# clickclack-mk-1_1-a.net
KiCad netlist of a schematic drawn in EAGLE
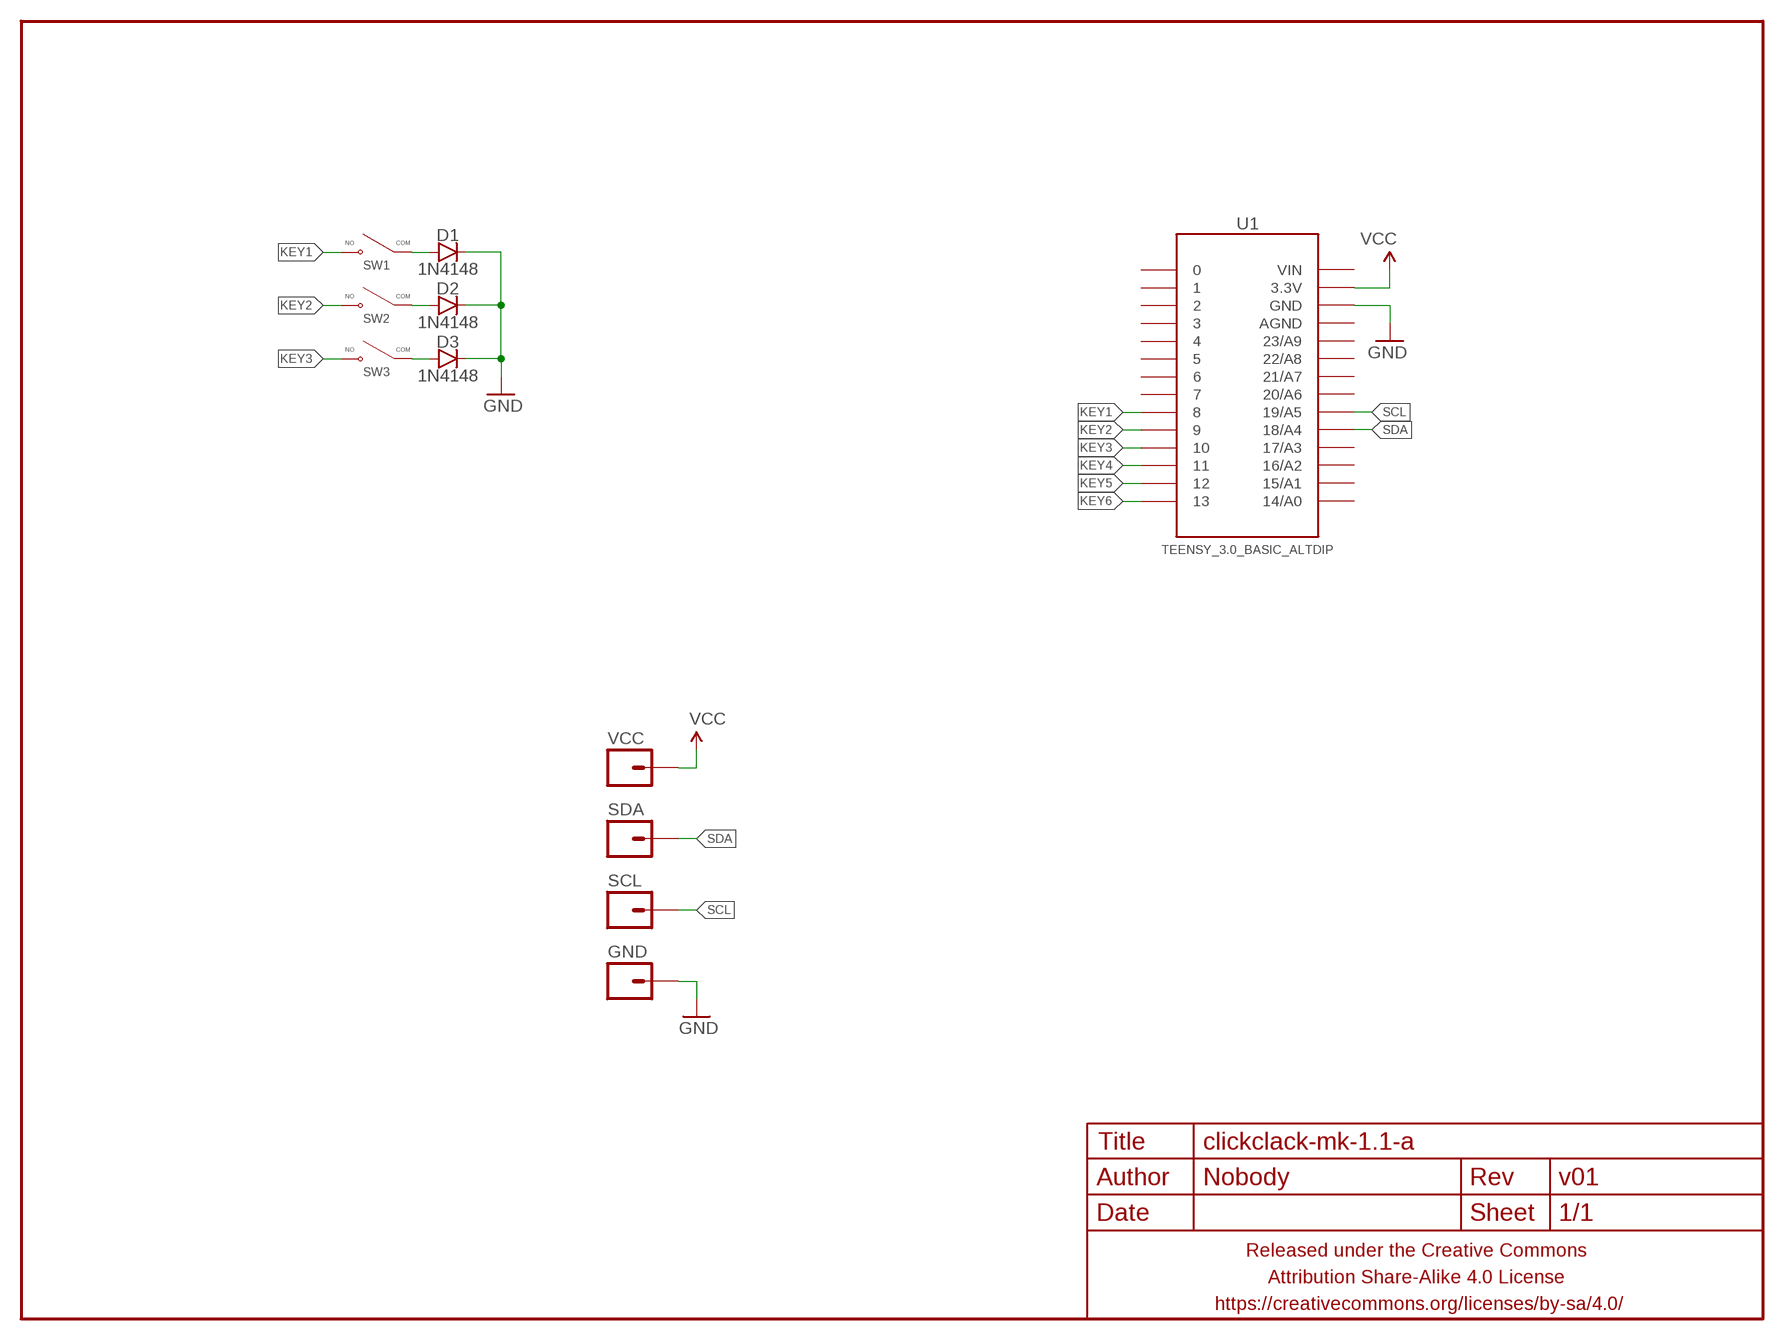
[diagram p0: schematic, sheet 1]

(export (version "E")
  (design (tool "Eeschema 10.0.6"))
  (components
    (comp (ref "D1")
      (value "1N4148")
      (footprint "eagle-import:DIODE-7.62MM")
      (libsource (lib "eagle-import") (part "DIODEPTH-7.62MM"))
    )
    (comp (ref "D2")
      (value "1N4148")
      (footprint "eagle-import:DIODE-7.62MM")
      (libsource (lib "eagle-import") (part "DIODEPTH-7.62MM"))
    )
    (comp (ref "D3")
      (value "1N4148")
      (footprint "eagle-import:DIODE-7.62MM")
      (libsource (lib "eagle-import") (part "DIODEPTH-7.62MM"))
    )
    (comp (ref "FRAME1")
      (value "FRAME-LETTERNO_PACKAGE")
      (footprint "eagle-import:DUMMY")
      (fields (field (name "DESIGNER") "Nobody"))
      (libsource (lib "eagle-import") (part "FRAME-LETTERNO_PACKAGE"))
    )
    (comp (ref "GND")
      (value "M01PTH")
      (footprint "eagle-import:1X01")
      (libsource (lib "eagle-import") (part "M01PTH"))
    )
    (comp (ref "SCL")
      (value "M01PTH")
      (footprint "eagle-import:1X01")
      (libsource (lib "eagle-import") (part "M01PTH"))
    )
    (comp (ref "SDA")
      (value "M01PTH")
      (footprint "eagle-import:1X01")
      (libsource (lib "eagle-import") (part "M01PTH"))
    )
    (comp (ref "SW1")
      (value "CHERRY-MXNONUBS")
      (footprint "eagle-import:CHERRY-MX-NONUBS")
      (libsource (lib "eagle-import") (part "CHERRY-MXNONUBS"))
    )
    (comp (ref "SW2")
      (value "CHERRY-MXNONUBS")
      (footprint "eagle-import:CHERRY-MX-NONUBS")
      (libsource (lib "eagle-import") (part "CHERRY-MXNONUBS"))
    )
    (comp (ref "SW3")
      (value "CHERRY-MXNONUBS")
      (footprint "eagle-import:CHERRY-MX-NONUBS")
      (libsource (lib "eagle-import") (part "CHERRY-MXNONUBS"))
    )
    (comp (ref "U1")
      (value "TEENSY_3.0_BASIC_ALTDIP")
      (footprint "eagle-import:TEENSY_3.0_BASIC_ALT2")
      (libsource (lib "eagle-import") (part "TEENSY_3.0_BASIC_ALTDIP"))
    )
    (comp (ref "VCC")
      (value "M01PTH")
      (footprint "eagle-import:1X01")
      (libsource (lib "eagle-import") (part "M01PTH"))
    )
  )
  (nets
    (net (code "1") (name "/AGND") (class "Default")
      (node (ref "U1") (pin "AGND") (pinfunction "AGND_AGND") (pintype "power_in"))
    )
    (net (code "2") (name "/VIN") (class "Default")
      (node (ref "U1") (pin "VIN") (pinfunction "VIN_VIN") (pintype "power_in"))
    )
    (net (code "3") (name "GND") (class "Default")
      (node (ref "D1") (pin "K") (pinfunction "C_K") (pintype "passive"))
      (node (ref "D2") (pin "K") (pinfunction "C_K") (pintype "passive"))
      (node (ref "D3") (pin "K") (pinfunction "C_K") (pintype "passive"))
      (node (ref "GND") (pin "1") (pinfunction "1_1") (pintype "passive"))
      (node (ref "U1") (pin "GND") (pinfunction "GND_GND") (pintype "power_in"))
    )
    (net (code "4") (name "KEY1") (class "Default")
      (node (ref "SW1") (pin "2") (pinfunction "NO_2") (pintype "bidirectional"))
      (node (ref "U1") (pin "8") (pinfunction "8_8") (pintype "bidirectional"))
    )
    (net (code "5") (name "KEY2") (class "Default")
      (node (ref "SW2") (pin "2") (pinfunction "NO_2") (pintype "bidirectional"))
      (node (ref "U1") (pin "9") (pinfunction "9_9") (pintype "bidirectional"))
    )
    (net (code "6") (name "KEY3") (class "Default")
      (node (ref "SW3") (pin "2") (pinfunction "NO_2") (pintype "bidirectional"))
      (node (ref "U1") (pin "10") (pinfunction "10_10") (pintype "bidirectional"))
    )
    (net (code "7") (name "KEY4") (class "Default")
      (node (ref "U1") (pin "11") (pinfunction "11_11") (pintype "bidirectional"))
    )
    (net (code "8") (name "KEY5") (class "Default")
      (node (ref "U1") (pin "12") (pinfunction "12_12") (pintype "bidirectional"))
    )
    (net (code "9") (name "KEY6") (class "Default")
      (node (ref "U1") (pin "13") (pinfunction "13_13") (pintype "bidirectional"))
    )
    (net (code "10") (name "Net-(SW1-COM)") (class "Default")
      (node (ref "D1") (pin "A") (pinfunction "A_A") (pintype "passive"))
      (node (ref "SW1") (pin "1") (pinfunction "COM_1") (pintype "bidirectional"))
    )
    (net (code "11") (name "Net-(SW2-COM)") (class "Default")
      (node (ref "D2") (pin "A") (pinfunction "A_A") (pintype "passive"))
      (node (ref "SW2") (pin "1") (pinfunction "COM_1") (pintype "bidirectional"))
    )
    (net (code "12") (name "Net-(SW3-COM)") (class "Default")
      (node (ref "D3") (pin "A") (pinfunction "A_A") (pintype "passive"))
      (node (ref "SW3") (pin "1") (pinfunction "COM_1") (pintype "bidirectional"))
    )
    (net (code "13") (name "SCL") (class "Default")
      (node (ref "SCL") (pin "1") (pinfunction "1_1") (pintype "passive"))
      (node (ref "U1") (pin "19/A5") (pinfunction "19/A5_19/A5") (pintype "bidirectional"))
    )
    (net (code "14") (name "SDA") (class "Default")
      (node (ref "SDA") (pin "1") (pinfunction "1_1") (pintype "passive"))
      (node (ref "U1") (pin "18/A4") (pinfunction "18/A4_18/A4") (pintype "bidirectional"))
    )
    (net (code "15") (name "VCC") (class "Default")
      (node (ref "U1") (pin "3.3V") (pinfunction "3.3V_3.3V") (pintype "power_in"))
      (node (ref "VCC") (pin "1") (pinfunction "1_1") (pintype "passive"))
    )
    (net (code "16") (name "unconnected-(U1-Pad0)") (class "Default")
      (node (ref "U1") (pin "0") (pinfunction "0_0") (pintype "bidirectional"))
    )
    (net (code "17") (name "unconnected-(U1-Pad1)") (class "Default")
      (node (ref "U1") (pin "1") (pinfunction "1_1") (pintype "bidirectional"))
    )
    (net (code "18") (name "unconnected-(U1-Pad2)") (class "Default")
      (node (ref "U1") (pin "2") (pinfunction "2_2") (pintype "bidirectional"))
    )
    (net (code "19") (name "unconnected-(U1-Pad3)") (class "Default")
      (node (ref "U1") (pin "3") (pinfunction "3_3") (pintype "bidirectional"))
    )
    (net (code "20") (name "unconnected-(U1-Pad4)") (class "Default")
      (node (ref "U1") (pin "4") (pinfunction "4_4") (pintype "bidirectional"))
    )
    (net (code "21") (name "unconnected-(U1-Pad5)") (class "Default")
      (node (ref "U1") (pin "5") (pinfunction "5_5") (pintype "bidirectional"))
    )
    (net (code "22") (name "unconnected-(U1-Pad6)") (class "Default")
      (node (ref "U1") (pin "6") (pinfunction "6_6") (pintype "bidirectional"))
    )
    (net (code "23") (name "unconnected-(U1-Pad7)") (class "Default")
      (node (ref "U1") (pin "7") (pinfunction "7_7") (pintype "bidirectional"))
    )
    (net (code "24") (name "unconnected-(U1-Pad14{slash}A0)") (class "Default")
      (node (ref "U1") (pin "14/A0") (pinfunction "14/A0_14/A0") (pintype "bidirectional"))
    )
    (net (code "25") (name "unconnected-(U1-Pad15{slash}A1)") (class "Default")
      (node (ref "U1") (pin "15/A1") (pinfunction "15/A1_15/A1") (pintype "bidirectional"))
    )
    (net (code "26") (name "unconnected-(U1-Pad16{slash}A2)") (class "Default")
      (node (ref "U1") (pin "16/A2") (pinfunction "16/A2_16/A2") (pintype "bidirectional"))
    )
    (net (code "27") (name "unconnected-(U1-Pad17{slash}A3)") (class "Default")
      (node (ref "U1") (pin "17/A3") (pinfunction "17/A3_17/A3") (pintype "bidirectional"))
    )
    (net (code "28") (name "unconnected-(U1-Pad20{slash}A6)") (class "Default")
      (node (ref "U1") (pin "20/A6") (pinfunction "20/A6_20/A6") (pintype "bidirectional"))
    )
    (net (code "29") (name "unconnected-(U1-Pad21{slash}A7)") (class "Default")
      (node (ref "U1") (pin "21/A7") (pinfunction "21/A7_21/A7") (pintype "bidirectional"))
    )
    (net (code "30") (name "unconnected-(U1-Pad22{slash}A8)") (class "Default")
      (node (ref "U1") (pin "22/A8") (pinfunction "22/A8_22/A8") (pintype "bidirectional"))
    )
    (net (code "31") (name "unconnected-(U1-Pad23{slash}A9)") (class "Default")
      (node (ref "U1") (pin "23/A9") (pinfunction "23/A9_23/A9") (pintype "bidirectional"))
    )
  )
)
